# MCU.net
KiCad netlist of a schematic drawn in Altium Designer
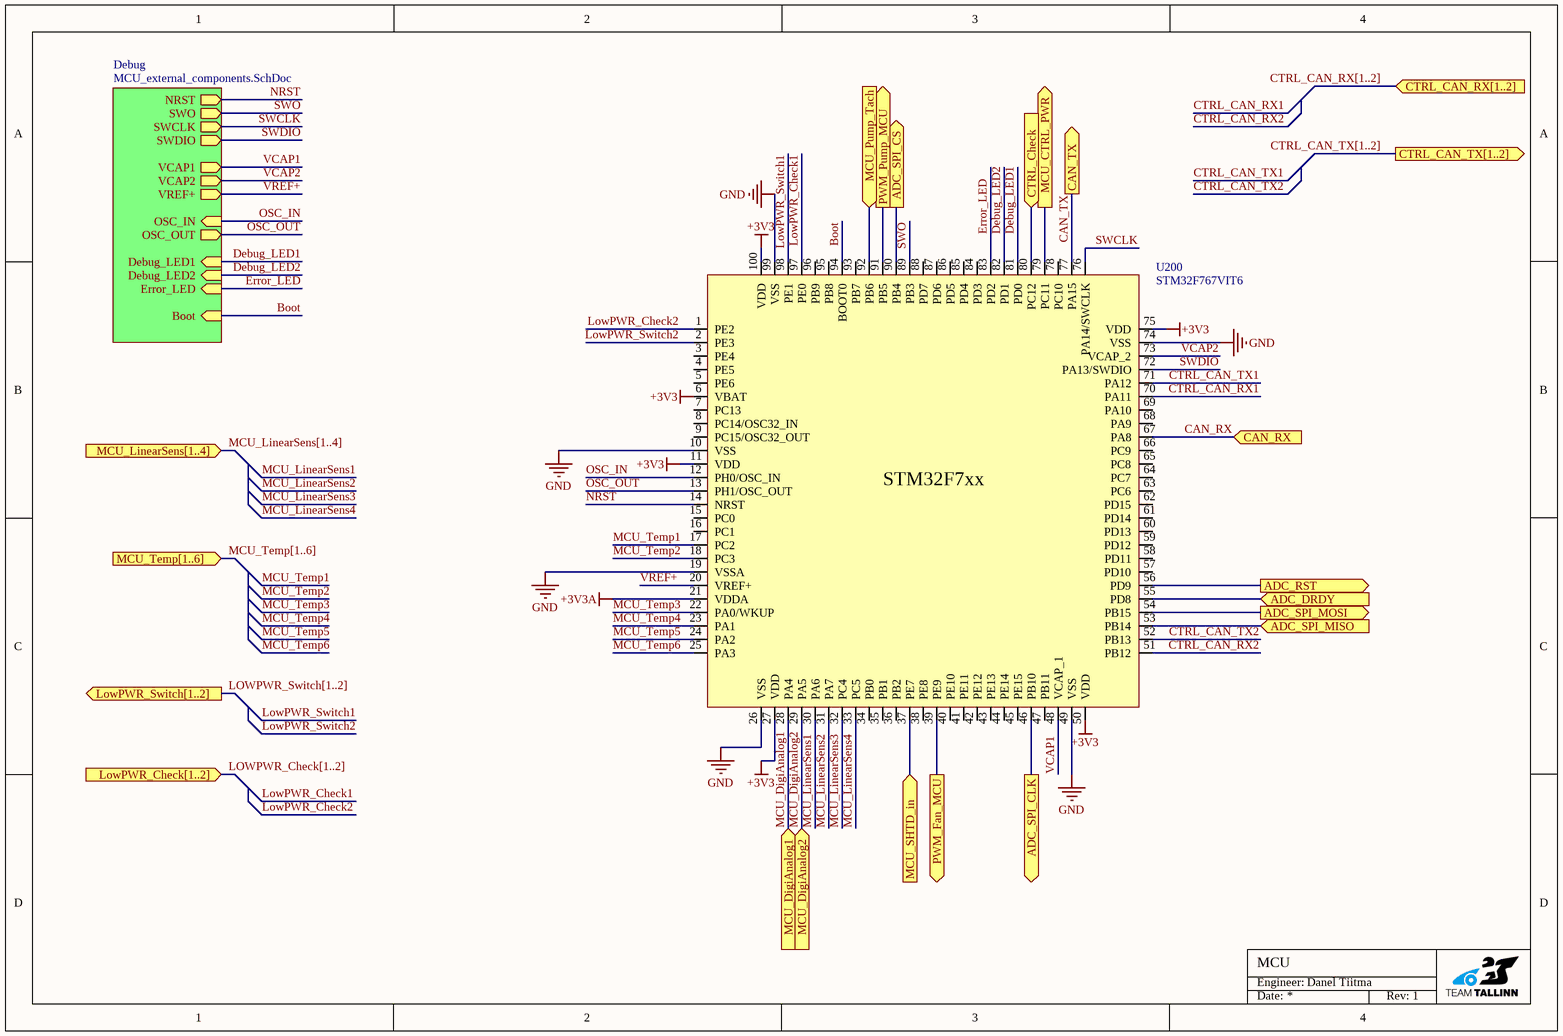
[diagram p0: MCU.SchDoc]

(export (version "E")
  (design (tool "Eeschema 10.0.6"))
  (components
    (comp (ref "U200")
      (value "STM32F767VIT6")
      (footprint "LQFP-100")
      (description "RISC Microcontroller, 32-Bit, 216MHz")
      (fields (field (name "MANUFACTURER") "STMICROELECTRONICS"))
      (libsource (lib "Formula Student Team Tallinn (Estonia)") (part "STM32F7 100-pin"))
    )
  )
  (nets
    (net (code "5") (name "+3V3") (class "Default")
      (node (ref "U200") (pin "100") (pinfunction "VDD_100") (pintype "passive"))
      (node (ref "U200") (pin "11") (pinfunction "VDD_11") (pintype "passive"))
      (node (ref "U200") (pin "27") (pinfunction "VDD_27") (pintype "passive"))
      (node (ref "U200") (pin "50") (pinfunction "VDD_50") (pintype "passive"))
      (node (ref "U200") (pin "6") (pinfunction "VBAT_6") (pintype "passive"))
      (node (ref "U200") (pin "75") (pinfunction "VDD_75") (pintype "passive"))
    )
    (net (code "6") (name "+3V3A") (class "Default")
      (node (ref "U200") (pin "21") (pinfunction "VDDA_21") (pintype "passive"))
    )
    (net (code "7") (name "/ADC_DRDY") (class "Default")
      (node (ref "U200") (pin "55") (pinfunction "PD8_55") (pintype "passive"))
    )
    (net (code "8") (name "/ADC_RST") (class "Default")
      (node (ref "U200") (pin "56") (pinfunction "PD9_56") (pintype "passive"))
    )
    (net (code "9") (name "/ADC_SPI_CLK") (class "Default")
      (node (ref "U200") (pin "46") (pinfunction "PB10_46") (pintype "passive"))
    )
    (net (code "10") (name "/ADC_SPI_CS") (class "Default")
      (node (ref "U200") (pin "90") (pinfunction "PB4_90") (pintype "passive"))
    )
    (net (code "11") (name "/ADC_SPI_MISO") (class "Default")
      (node (ref "U200") (pin "53") (pinfunction "PB14_53") (pintype "passive"))
    )
    (net (code "12") (name "/ADC_SPI_MOSI") (class "Default")
      (node (ref "U200") (pin "54") (pinfunction "PB15_54") (pintype "passive"))
    )
    (net (code "13") (name "/Boot") (class "Default")
      (node (ref "U200") (pin "94") (pinfunction "BOOT0_94") (pintype "passive"))
    )
    (net (code "14") (name "/CAN_RX") (class "Default")
      (node (ref "U200") (pin "67") (pinfunction "PA8_67") (pintype "passive"))
    )
    (net (code "15") (name "/CAN_TX") (class "Default")
      (node (ref "U200") (pin "77") (pinfunction "PA15_77") (pintype "passive"))
    )
    (net (code "16") (name "/CTRL_CAN_RX1") (class "Default")
      (node (ref "U200") (pin "70") (pinfunction "PA11_70") (pintype "passive"))
    )
    (net (code "17") (name "/CTRL_CAN_RX2") (class "Default")
      (node (ref "U200") (pin "51") (pinfunction "PB12_51") (pintype "passive"))
    )
    (net (code "19") (name "/CTRL_CAN_TX1") (class "Default")
      (node (ref "U200") (pin "71") (pinfunction "PA12_71") (pintype "passive"))
    )
    (net (code "20") (name "/CTRL_CAN_TX2") (class "Default")
      (node (ref "U200") (pin "52") (pinfunction "PB13_52") (pintype "passive"))
    )
    (net (code "22") (name "/CTRL_Check") (class "Default")
      (node (ref "U200") (pin "80") (pinfunction "PC12_80") (pintype "passive"))
    )
    (net (code "23") (name "/Debug_LED1") (class "Default")
      (node (ref "U200") (pin "81") (pinfunction "PD0_81") (pintype "passive"))
    )
    (net (code "24") (name "/Debug_LED2") (class "Default")
      (node (ref "U200") (pin "82") (pinfunction "PD1_82") (pintype "passive"))
    )
    (net (code "25") (name "/Error_LED") (class "Default")
      (node (ref "U200") (pin "83") (pinfunction "PD2_83") (pintype "passive"))
    )
    (net (code "26") (name "/LOWPWR_Check1") (class "Default")
      (node (ref "U200") (pin "97") (pinfunction "PE0_97") (pintype "passive"))
    )
    (net (code "27") (name "/LOWPWR_Check2") (class "Default")
      (node (ref "U200") (pin "1") (pinfunction "PE2_1") (pintype "passive"))
    )
    (net (code "29") (name "/LOWPWR_Switch1") (class "Default")
      (node (ref "U200") (pin "98") (pinfunction "PE1_98") (pintype "passive"))
    )
    (net (code "30") (name "/LOWPWR_Switch2") (class "Default")
      (node (ref "U200") (pin "2") (pinfunction "PE3_2") (pintype "passive"))
    )
    (net (code "32") (name "/MCU_CTRL_PWR") (class "Default")
      (node (ref "U200") (pin "79") (pinfunction "PC11_79") (pintype "passive"))
    )
    (net (code "33") (name "/MCU_DigiAnalog1") (class "Default")
      (node (ref "U200") (pin "28") (pinfunction "PA4_28") (pintype "passive"))
    )
    (net (code "34") (name "/MCU_DigiAnalog2") (class "Default")
      (node (ref "U200") (pin "29") (pinfunction "PA5_29") (pintype "passive"))
    )
    (net (code "35") (name "/MCU_LinearSens1") (class "Default")
      (node (ref "U200") (pin "30") (pinfunction "PA6_30") (pintype "passive"))
    )
    (net (code "36") (name "/MCU_LinearSens2") (class "Default")
      (node (ref "U200") (pin "31") (pinfunction "PA7_31") (pintype "passive"))
    )
    (net (code "37") (name "/MCU_LinearSens3") (class "Default")
      (node (ref "U200") (pin "32") (pinfunction "PC4_32") (pintype "passive"))
    )
    (net (code "38") (name "/MCU_LinearSens4") (class "Default")
      (node (ref "U200") (pin "33") (pinfunction "PC5_33") (pintype "passive"))
    )
    (net (code "40") (name "/MCU_Pump_Tach") (class "Default")
      (node (ref "U200") (pin "92") (pinfunction "PB6_92") (pintype "passive"))
    )
    (net (code "41") (name "/MCU_SHTD_in") (class "Default")
      (node (ref "U200") (pin "37") (pinfunction "PE7_37") (pintype "passive"))
    )
    (net (code "42") (name "/MCU_Temp1") (class "Default")
      (node (ref "U200") (pin "17") (pinfunction "PC2_17") (pintype "passive"))
    )
    (net (code "43") (name "/MCU_Temp2") (class "Default")
      (node (ref "U200") (pin "18") (pinfunction "PC3_18") (pintype "passive"))
    )
    (net (code "44") (name "/MCU_Temp3") (class "Default")
      (node (ref "U200") (pin "22") (pinfunction "PA0/WKUP_22") (pintype "passive"))
    )
    (net (code "45") (name "/MCU_Temp4") (class "Default")
      (node (ref "U200") (pin "23") (pinfunction "PA1_23") (pintype "passive"))
    )
    (net (code "46") (name "/MCU_Temp5") (class "Default")
      (node (ref "U200") (pin "24") (pinfunction "PA2_24") (pintype "passive"))
    )
    (net (code "47") (name "/MCU_Temp6") (class "Default")
      (node (ref "U200") (pin "25") (pinfunction "PA3_25") (pintype "passive"))
    )
    (net (code "49") (name "/NRST") (class "Default")
      (node (ref "U200") (pin "14") (pinfunction "NRST_14") (pintype "passive"))
    )
    (net (code "50") (name "/OSC_IN") (class "Default")
      (node (ref "U200") (pin "12") (pinfunction "PH0/OSC_IN_12") (pintype "passive"))
    )
    (net (code "51") (name "/OSC_OUT") (class "Default")
      (node (ref "U200") (pin "13") (pinfunction "PH1/OSC_OUT_13") (pintype "passive"))
    )
    (net (code "52") (name "/PWM_Fan_MCU") (class "Default")
      (node (ref "U200") (pin "39") (pinfunction "PE9_39") (pintype "passive"))
    )
    (net (code "53") (name "/PWM_Pump_MCU") (class "Default")
      (node (ref "U200") (pin "91") (pinfunction "PB5_91") (pintype "passive"))
    )
    (net (code "54") (name "/SWCLK") (class "Default")
      (node (ref "U200") (pin "76") (pinfunction "PA14/SWCLK_76") (pintype "passive"))
    )
    (net (code "55") (name "/SWDIO") (class "Default")
      (node (ref "U200") (pin "72") (pinfunction "PA13/SWDIO_72") (pintype "passive"))
    )
    (net (code "56") (name "/SWO") (class "Default")
      (node (ref "U200") (pin "89") (pinfunction "PB3_89") (pintype "passive"))
    )
    (net (code "57") (name "/VCAP1") (class "Default")
      (node (ref "U200") (pin "48") (pinfunction "VCAP_1_48") (pintype "passive"))
    )
    (net (code "58") (name "/VCAP2") (class "Default")
      (node (ref "U200") (pin "73") (pinfunction "VCAP_2_73") (pintype "passive"))
    )
    (net (code "59") (name "/VREF+") (class "Default")
      (node (ref "U200") (pin "20") (pinfunction "VREF+_20") (pintype "passive"))
    )
    (net (code "60") (name "GND") (class "Default")
      (node (ref "U200") (pin "10") (pinfunction "VSS_10") (pintype "passive"))
      (node (ref "U200") (pin "19") (pinfunction "VSSA_19") (pintype "passive"))
      (node (ref "U200") (pin "26") (pinfunction "VSS_26") (pintype "passive"))
      (node (ref "U200") (pin "49") (pinfunction "VSS_49") (pintype "passive"))
      (node (ref "U200") (pin "74") (pinfunction "VSS_74") (pintype "passive"))
      (node (ref "U200") (pin "99") (pinfunction "VSS_99") (pintype "passive"))
    )
    (net (code "61") (name "unconnected-(U200-PA9-Pad68)") (class "Default")
      (node (ref "U200") (pin "68") (pinfunction "PA9_68") (pintype "passive"))
    )
    (net (code "62") (name "unconnected-(U200-PA10-Pad69)") (class "Default")
      (node (ref "U200") (pin "69") (pinfunction "PA10_69") (pintype "passive"))
    )
    (net (code "63") (name "unconnected-(U200-PB0-Pad34)") (class "Default")
      (node (ref "U200") (pin "34") (pinfunction "PB0_34") (pintype "passive"))
    )
    (net (code "64") (name "unconnected-(U200-PB1-Pad35)") (class "Default")
      (node (ref "U200") (pin "35") (pinfunction "PB1_35") (pintype "passive"))
    )
    (net (code "65") (name "unconnected-(U200-PB2-Pad36)") (class "Default")
      (node (ref "U200") (pin "36") (pinfunction "PB2_36") (pintype "passive"))
    )
    (net (code "66") (name "unconnected-(U200-PB7-Pad93)") (class "Default")
      (node (ref "U200") (pin "93") (pinfunction "PB7_93") (pintype "passive"))
    )
    (net (code "67") (name "unconnected-(U200-PB8-Pad95)") (class "Default")
      (node (ref "U200") (pin "95") (pinfunction "PB8_95") (pintype "passive"))
    )
    (net (code "68") (name "unconnected-(U200-PB9-Pad96)") (class "Default")
      (node (ref "U200") (pin "96") (pinfunction "PB9_96") (pintype "passive"))
    )
    (net (code "69") (name "unconnected-(U200-PB11-Pad47)") (class "Default")
      (node (ref "U200") (pin "47") (pinfunction "PB11_47") (pintype "passive"))
    )
    (net (code "70") (name "unconnected-(U200-PC0-Pad15)") (class "Default")
      (node (ref "U200") (pin "15") (pinfunction "PC0_15") (pintype "passive"))
    )
    (net (code "71") (name "unconnected-(U200-PC1-Pad16)") (class "Default")
      (node (ref "U200") (pin "16") (pinfunction "PC1_16") (pintype "passive"))
    )
    (net (code "72") (name "unconnected-(U200-PC6-Pad63)") (class "Default")
      (node (ref "U200") (pin "63") (pinfunction "PC6_63") (pintype "passive"))
    )
    (net (code "73") (name "unconnected-(U200-PC7-Pad64)") (class "Default")
      (node (ref "U200") (pin "64") (pinfunction "PC7_64") (pintype "passive"))
    )
    (net (code "74") (name "unconnected-(U200-PC8-Pad65)") (class "Default")
      (node (ref "U200") (pin "65") (pinfunction "PC8_65") (pintype "passive"))
    )
    (net (code "75") (name "unconnected-(U200-PC9-Pad66)") (class "Default")
      (node (ref "U200") (pin "66") (pinfunction "PC9_66") (pintype "passive"))
    )
    (net (code "76") (name "unconnected-(U200-PC10-Pad78)") (class "Default")
      (node (ref "U200") (pin "78") (pinfunction "PC10_78") (pintype "passive"))
    )
    (net (code "77") (name "unconnected-(U200-PC13-Pad7)") (class "Default")
      (node (ref "U200") (pin "7") (pinfunction "PC13_7") (pintype "passive"))
    )
    (net (code "78") (name "unconnected-(U200-PC14{slash}OSC32_IN-Pad8)") (class "Default")
      (node (ref "U200") (pin "8") (pinfunction "PC14/OSC32_IN_8") (pintype "passive"))
    )
    (net (code "79") (name "unconnected-(U200-PC15{slash}OSC32_OUT-Pad9)") (class "Default")
      (node (ref "U200") (pin "9") (pinfunction "PC15/OSC32_OUT_9") (pintype "passive"))
    )
    (net (code "80") (name "unconnected-(U200-PD3-Pad84)") (class "Default")
      (node (ref "U200") (pin "84") (pinfunction "PD3_84") (pintype "passive"))
    )
    (net (code "81") (name "unconnected-(U200-PD4-Pad85)") (class "Default")
      (node (ref "U200") (pin "85") (pinfunction "PD4_85") (pintype "passive"))
    )
    (net (code "82") (name "unconnected-(U200-PD5-Pad86)") (class "Default")
      (node (ref "U200") (pin "86") (pinfunction "PD5_86") (pintype "passive"))
    )
    (net (code "83") (name "unconnected-(U200-PD6-Pad87)") (class "Default")
      (node (ref "U200") (pin "87") (pinfunction "PD6_87") (pintype "passive"))
    )
    (net (code "84") (name "unconnected-(U200-PD7-Pad88)") (class "Default")
      (node (ref "U200") (pin "88") (pinfunction "PD7_88") (pintype "passive"))
    )
    (net (code "85") (name "unconnected-(U200-PD10-Pad57)") (class "Default")
      (node (ref "U200") (pin "57") (pinfunction "PD10_57") (pintype "passive"))
    )
    (net (code "86") (name "unconnected-(U200-PD11-Pad58)") (class "Default")
      (node (ref "U200") (pin "58") (pinfunction "PD11_58") (pintype "passive"))
    )
    (net (code "87") (name "unconnected-(U200-PD12-Pad59)") (class "Default")
      (node (ref "U200") (pin "59") (pinfunction "PD12_59") (pintype "passive"))
    )
    (net (code "88") (name "unconnected-(U200-PD13-Pad60)") (class "Default")
      (node (ref "U200") (pin "60") (pinfunction "PD13_60") (pintype "passive"))
    )
    (net (code "89") (name "unconnected-(U200-PD14-Pad61)") (class "Default")
      (node (ref "U200") (pin "61") (pinfunction "PD14_61") (pintype "passive"))
    )
    (net (code "90") (name "unconnected-(U200-PD15-Pad62)") (class "Default")
      (node (ref "U200") (pin "62") (pinfunction "PD15_62") (pintype "passive"))
    )
    (net (code "91") (name "unconnected-(U200-PE4-Pad3)") (class "Default")
      (node (ref "U200") (pin "3") (pinfunction "PE4_3") (pintype "passive"))
    )
    (net (code "92") (name "unconnected-(U200-PE5-Pad4)") (class "Default")
      (node (ref "U200") (pin "4") (pinfunction "PE5_4") (pintype "passive"))
    )
    (net (code "93") (name "unconnected-(U200-PE6-Pad5)") (class "Default")
      (node (ref "U200") (pin "5") (pinfunction "PE6_5") (pintype "passive"))
    )
    (net (code "94") (name "unconnected-(U200-PE8-Pad38)") (class "Default")
      (node (ref "U200") (pin "38") (pinfunction "PE8_38") (pintype "passive"))
    )
    (net (code "95") (name "unconnected-(U200-PE10-Pad40)") (class "Default")
      (node (ref "U200") (pin "40") (pinfunction "PE10_40") (pintype "passive"))
    )
    (net (code "96") (name "unconnected-(U200-PE11-Pad41)") (class "Default")
      (node (ref "U200") (pin "41") (pinfunction "PE11_41") (pintype "passive"))
    )
    (net (code "97") (name "unconnected-(U200-PE12-Pad42)") (class "Default")
      (node (ref "U200") (pin "42") (pinfunction "PE12_42") (pintype "passive"))
    )
    (net (code "98") (name "unconnected-(U200-PE13-Pad43)") (class "Default")
      (node (ref "U200") (pin "43") (pinfunction "PE13_43") (pintype "passive"))
    )
    (net (code "99") (name "unconnected-(U200-PE14-Pad44)") (class "Default")
      (node (ref "U200") (pin "44") (pinfunction "PE14_44") (pintype "passive"))
    )
    (net (code "100") (name "unconnected-(U200-PE15-Pad45)") (class "Default")
      (node (ref "U200") (pin "45") (pinfunction "PE15_45") (pintype "passive"))
    )
  )
)
